# Motor_ESC.net
KiCad netlist of a schematic drawn in Altium Designer
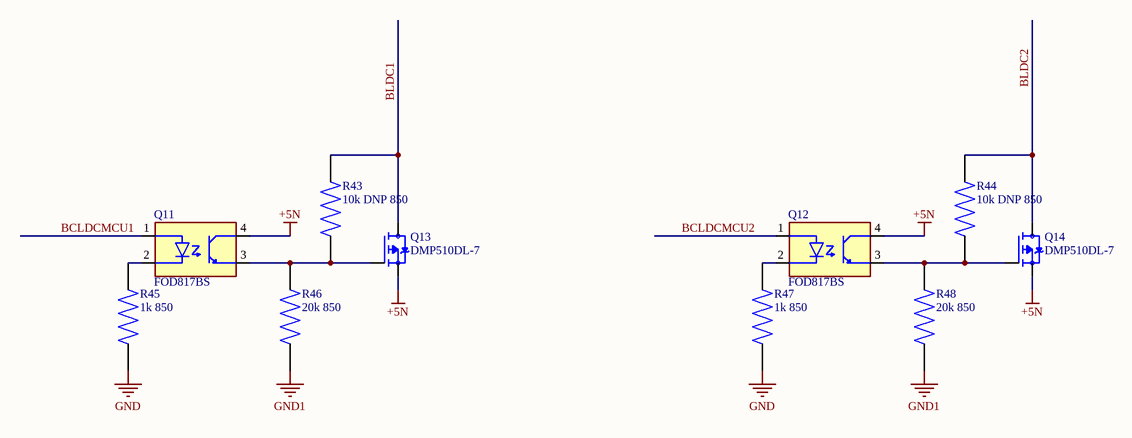
[diagram p0: Motor_ESC.SchDoc]

(export (version "E")
  (design (tool "Eeschema 10.0.6"))
  (components
    (comp (ref "Q11")
      (value "FOD817BS")
      (footprint "SOIC254P1016X385-4N")
      (description "Transistor Output Optocouplers Opto Phototransistor Output SM-DIP4")
      (fields (field (name "MF") "ON Semiconductor"))
      (libsource (lib "iee_altium") (part "FOD817BS"))
    )
    (comp (ref "Q12")
      (value "FOD817BS")
      (footprint "SOIC254P1016X385-4N")
      (description "Transistor Output Optocouplers Opto Phototransistor Output SM-DIP4")
      (fields (field (name "MF") "ON Semiconductor"))
      (libsource (lib "iee_altium") (part "FOD817BS"))
    )
    (comp (ref "Q13")
      (value "DMP510DL-7")
      (footprint "SOT91P240X110-3N - duplicate")
      (libsource (lib "iee_altium") (part "DMP510DL-7"))
    )
    (comp (ref "Q14")
      (value "DMP510DL-7")
      (footprint "SOT91P240X110-3N - duplicate")
      (libsource (lib "iee_altium") (part "DMP510DL-7"))
    )
    (comp (ref "R43")
      (value "10k DNP 850")
      (footprint "10k 850")
      (libsource (lib "iee_altium") (part "10k 850"))
    )
    (comp (ref "R44")
      (value "10k DNP 850")
      (footprint "10k 850")
      (libsource (lib "iee_altium") (part "10k 850"))
    )
    (comp (ref "R45") (value "1k 850") (footprint "10k 850") (libsource (lib "iee_altium") (part "10k 850")))
    (comp (ref "R46") (value "20k 850") (footprint "10k 850") (libsource (lib "iee_altium") (part "10k 850")))
    (comp (ref "R47") (value "1k 850") (footprint "10k 850") (libsource (lib "iee_altium") (part "10k 850")))
    (comp (ref "R48") (value "20k 850") (footprint "10k 850") (libsource (lib "iee_altium") (part "10k 850")))
  )
  (nets
    (net (code "1") (name "+5N") (class "Default")
      (node (ref "Q11") (pin "4") (pinfunction "COLLECTOR_4") (pintype "passive"))
      (node (ref "Q12") (pin "4") (pinfunction "COLLECTOR_4") (pintype "passive"))
      (node (ref "Q13") (pin "2") (pinfunction "S_2") (pintype "passive"))
      (node (ref "Q14") (pin "2") (pinfunction "S_2") (pintype "passive"))
    )
    (net (code "2") (name "/BCLDCMCU1") (class "Default")
      (node (ref "Q11") (pin "1") (pinfunction "ANODE_1") (pintype "passive"))
    )
    (net (code "3") (name "/BCLDCMCU2") (class "Default")
      (node (ref "Q12") (pin "1") (pinfunction "ANODE_1") (pintype "passive"))
    )
    (net (code "4") (name "/BLDC1") (class "Default")
      (node (ref "Q13") (pin "3") (pinfunction "D_3") (pintype "passive"))
      (node (ref "R43") (pin "1") (pinfunction "1_1") (pintype "passive"))
    )
    (net (code "5") (name "/BLDC2") (class "Default")
      (node (ref "Q14") (pin "3") (pinfunction "D_3") (pintype "passive"))
      (node (ref "R44") (pin "1") (pinfunction "1_1") (pintype "passive"))
    )
    (net (code "6") (name "GND") (class "Default")
      (node (ref "R45") (pin "2") (pinfunction "2_2") (pintype "passive"))
      (node (ref "R47") (pin "2") (pinfunction "2_2") (pintype "passive"))
    )
    (net (code "7") (name "GND1") (class "Default")
      (node (ref "R46") (pin "2") (pinfunction "2_2") (pintype "passive"))
      (node (ref "R48") (pin "2") (pinfunction "2_2") (pintype "passive"))
    )
    (net (code "8") (name "Net-(Q11-CATHODE)") (class "Default")
      (node (ref "Q11") (pin "2") (pinfunction "CATHODE_2") (pintype "passive"))
      (node (ref "R45") (pin "1") (pinfunction "1_1") (pintype "passive"))
    )
    (net (code "9") (name "Net-(Q11-EMITTER)") (class "Default")
      (node (ref "Q11") (pin "3") (pinfunction "EMITTER_3") (pintype "passive"))
      (node (ref "Q13") (pin "1") (pinfunction "G_1") (pintype "passive"))
      (node (ref "R43") (pin "2") (pinfunction "2_2") (pintype "passive"))
      (node (ref "R46") (pin "1") (pinfunction "1_1") (pintype "passive"))
    )
    (net (code "10") (name "Net-(Q12-CATHODE)") (class "Default")
      (node (ref "Q12") (pin "2") (pinfunction "CATHODE_2") (pintype "passive"))
      (node (ref "R47") (pin "1") (pinfunction "1_1") (pintype "passive"))
    )
    (net (code "11") (name "Net-(Q12-EMITTER)") (class "Default")
      (node (ref "Q12") (pin "3") (pinfunction "EMITTER_3") (pintype "passive"))
      (node (ref "Q14") (pin "1") (pinfunction "G_1") (pintype "passive"))
      (node (ref "R44") (pin "2") (pinfunction "2_2") (pintype "passive"))
      (node (ref "R48") (pin "1") (pinfunction "1_1") (pintype "passive"))
    )
  )
)
